# rotor.net
KiCad netlist of a schematic drawn in EAGLE
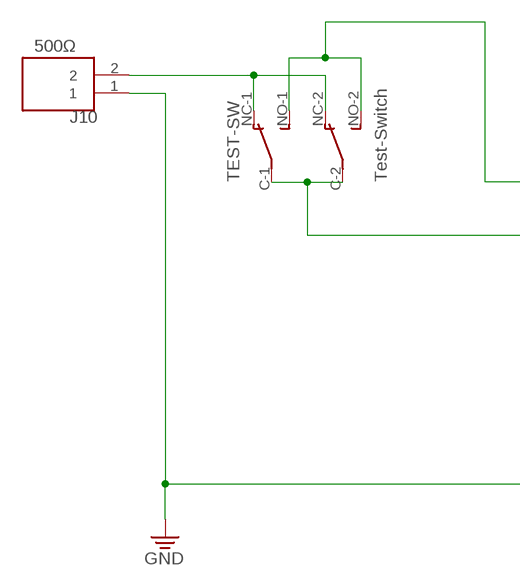
[diagram p0: schematic, sheet 1, part 1 of 2]
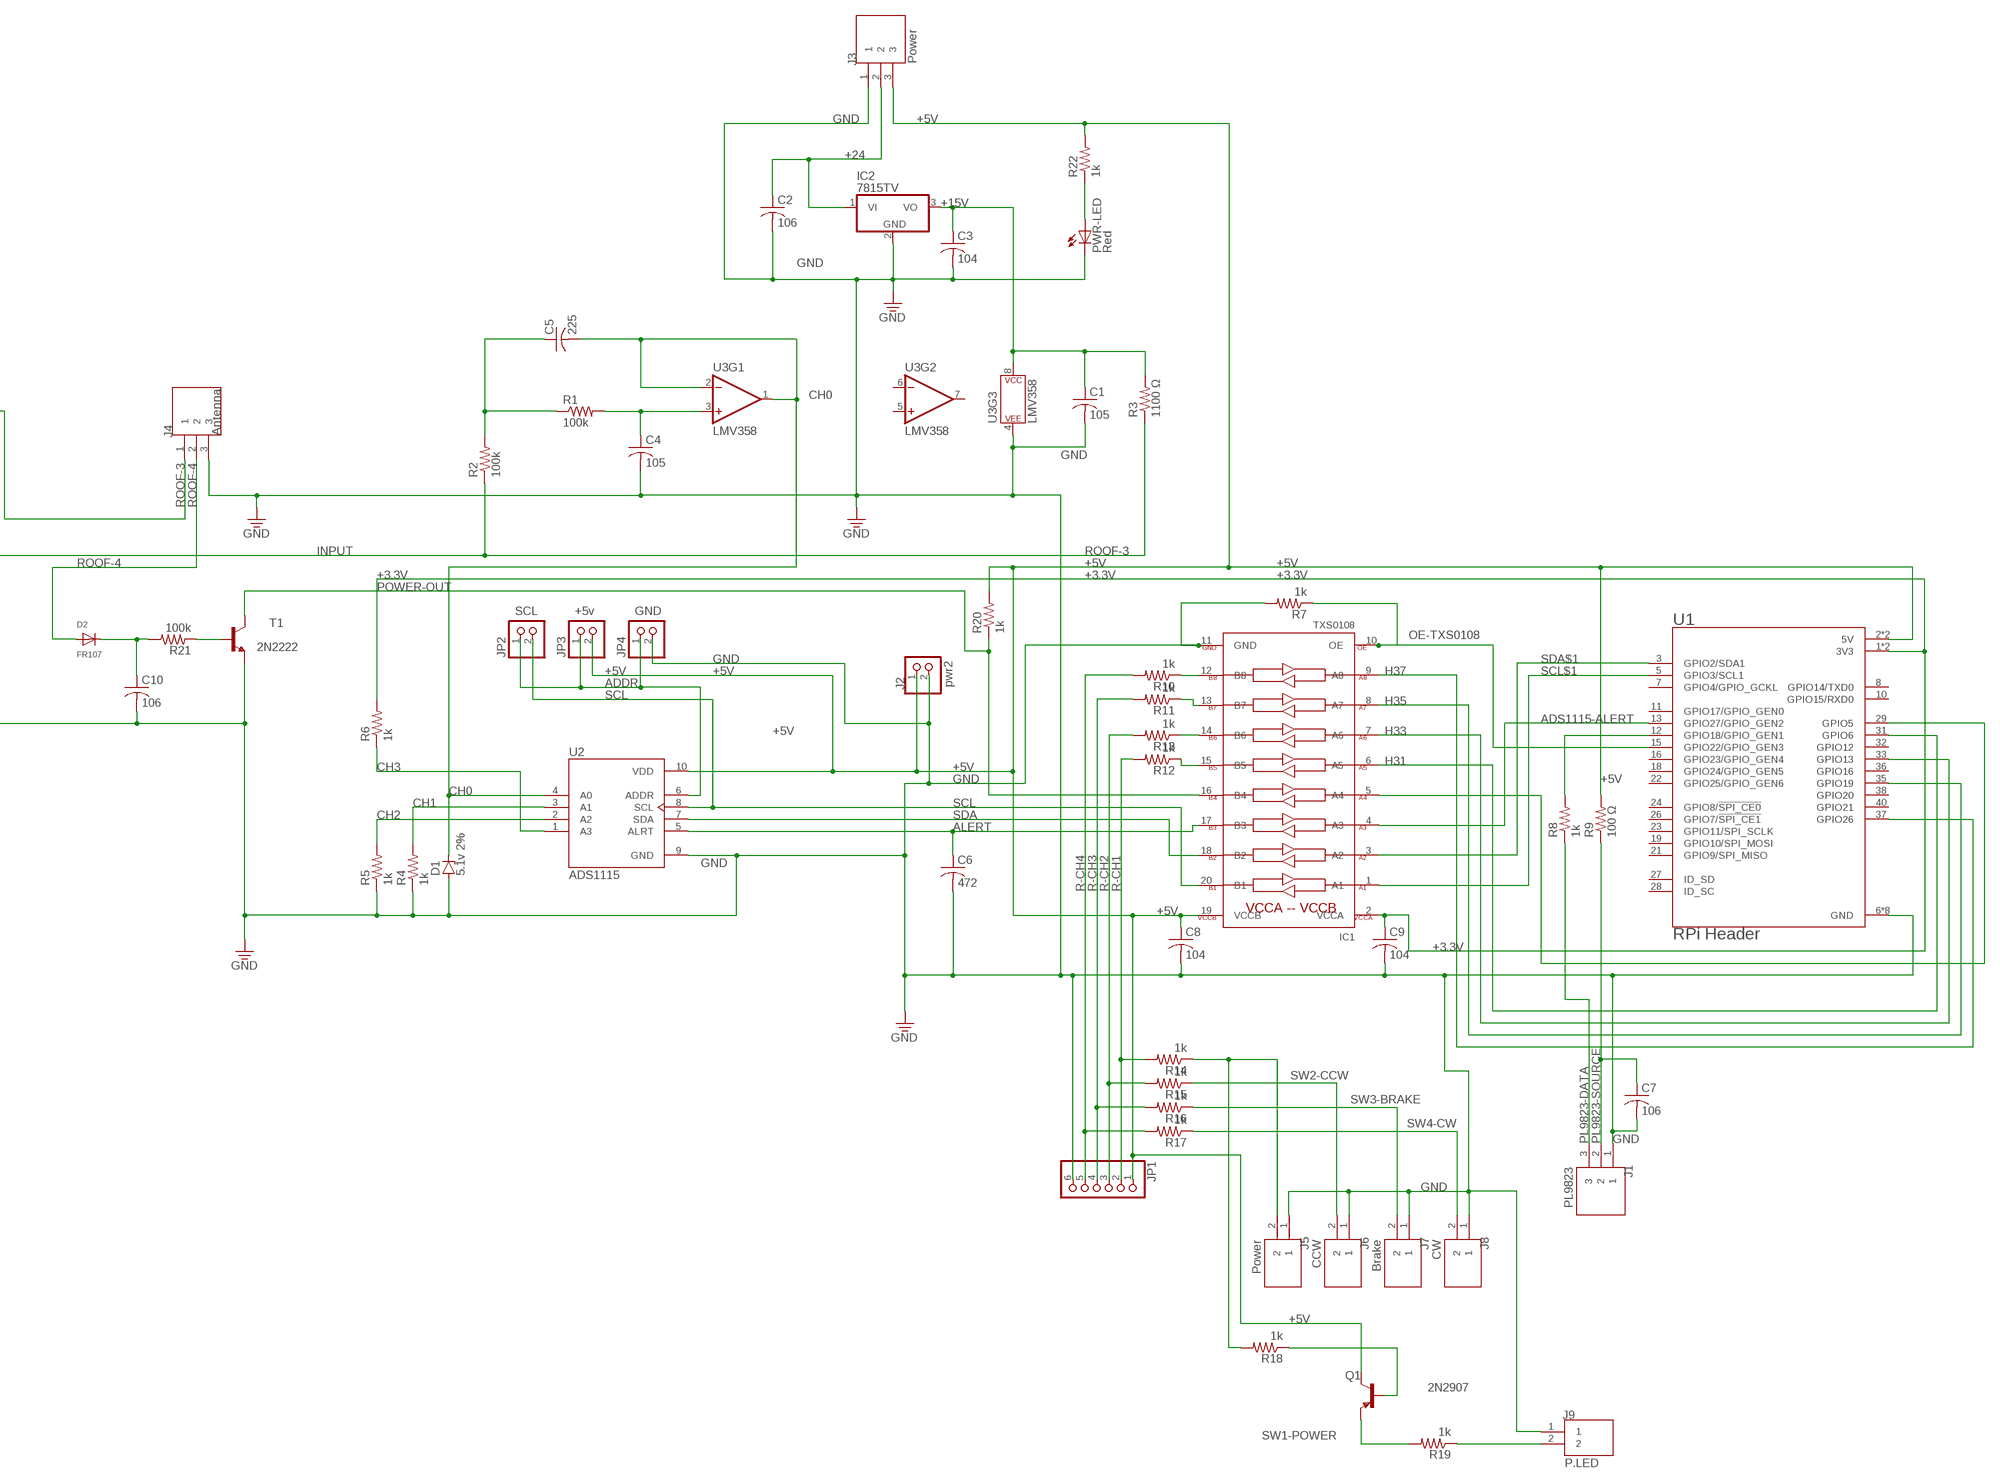
[diagram p1: schematic, sheet 1, part 2 of 2]

(export (version "E")
  (design (tool "Eeschema 10.0.6"))
  (components
    (comp (ref "C1")
      (value "105")
      (footprint "eagle-import:C0805")
      (libsource (lib "eagle-import") (part "C-USC0805"))
    )
    (comp (ref "C2")
      (value "106")
      (footprint "eagle-import:C0805")
      (libsource (lib "eagle-import") (part "C-USC0805"))
    )
    (comp (ref "C3")
      (value "104")
      (footprint "eagle-import:C0805")
      (libsource (lib "eagle-import") (part "C-USC0805"))
    )
    (comp (ref "C4")
      (value "105")
      (footprint "eagle-import:C0805")
      (libsource (lib "eagle-import") (part "C-USC0805"))
    )
    (comp (ref "C5")
      (value "225")
      (footprint "eagle-import:C0805")
      (libsource (lib "eagle-import") (part "C-USC0805"))
    )
    (comp (ref "C6")
      (value "472")
      (footprint "eagle-import:C0805")
      (libsource (lib "eagle-import") (part "C-USC0805"))
    )
    (comp (ref "C7")
      (value "106")
      (footprint "eagle-import:C0805")
      (libsource (lib "eagle-import") (part "C-USC0805"))
    )
    (comp (ref "C8")
      (value "104")
      (footprint "eagle-import:C0805")
      (libsource (lib "eagle-import") (part "C-USC0805"))
    )
    (comp (ref "C9")
      (value "104")
      (footprint "eagle-import:C0805")
      (libsource (lib "eagle-import") (part "C-USC0805"))
    )
    (comp (ref "C10")
      (value "106")
      (footprint "eagle-import:C0805")
      (libsource (lib "eagle-import") (part "C-USC0805"))
    )
    (comp (ref "D1")
      (value "5.1v 2%")
      (footprint "eagle-import:ZDIO-7.5")
      (libsource (lib "eagle-import") (part "ZENER-DIODEZD-7.5"))
    )
    (comp (ref "D2")
      (value "FR107")
      (footprint "eagle-import:SMADIODE")
      (libsource (lib "eagle-import") (part "DIODESMA"))
    )
    (comp (ref "IC1")
      (value "TXS0108")
      (footprint "eagle-import:TSSOP20")
      (fields (field (name "MF") "Texas Instruments") (field (name "MP") "TXS0108E"))
      (libsource (lib "eagle-import") (part "TXS0108EPWR"))
    )
    (comp (ref "IC2")
      (value "7815TV")
      (footprint "eagle-import:TO220V")
      (libsource (lib "eagle-import") (part "78TV15"))
    )
    (comp (ref "J1")
      (value "PL9823")
      (footprint "eagle-import:CUI_TB004-508-03BE")
      (fields (field (name "MF") "CUI Devices") (field (name "MP") "TB004 -508-03BE"))
      (libsource (lib "eagle-import") (part "TB004-508-03BE"))
    )
    (comp (ref "J2")
      (value "pwr2")
      (footprint "eagle-import:1X02")
      (libsource (lib "eagle-import") (part "pinhead_325_PINHD-1X2"))
    )
    (comp (ref "J3")
      (value "Power")
      (footprint "eagle-import:CUI_TB004-508-03BE")
      (fields (field (name "MF") "CUI Devices") (field (name "MP") "TB004 -508-03BE"))
      (libsource (lib "eagle-import") (part "TB004-508-03BE"))
    )
    (comp (ref "J4")
      (value "Antenna")
      (footprint "eagle-import:CUI_TB004-508-03BE")
      (fields (field (name "MF") "CUI Devices") (field (name "MP") "TB004 -508-03BE"))
      (libsource (lib "eagle-import") (part "TB004-508-03BE"))
    )
    (comp (ref "J5")
      (value "Power")
      (footprint "eagle-import:CUI_TB004-508-02BE")
      (fields (field (name "MF") "CUI Devices") (field (name "MP") "TB004-508-02BE"))
      (libsource (lib "eagle-import") (part "TB004-508-02BE"))
    )
    (comp (ref "J6")
      (value "CCW")
      (footprint "eagle-import:CUI_TB004-508-02BE")
      (fields (field (name "MF") "CUI Devices") (field (name "MP") "TB004-508-02BE"))
      (libsource (lib "eagle-import") (part "TB004-508-02BE"))
    )
    (comp (ref "J7")
      (value "Brake")
      (footprint "eagle-import:CUI_TB004-508-02BE")
      (fields (field (name "MF") "CUI Devices") (field (name "MP") "TB004-508-02BE"))
      (libsource (lib "eagle-import") (part "TB004-508-02BE"))
    )
    (comp (ref "J8")
      (value "CW")
      (footprint "eagle-import:CUI_TB004-508-02BE")
      (fields (field (name "MF") "CUI Devices") (field (name "MP") "TB004-508-02BE"))
      (libsource (lib "eagle-import") (part "TB004-508-02BE"))
    )
    (comp (ref "J9")
      (value "P.LED")
      (footprint "eagle-import:CUI_TB004-508-02BE")
      (fields (field (name "MF") "CUI Devices") (field (name "MP") "TB004-508-02BE"))
      (libsource (lib "eagle-import") (part "TB004-508-02BE"))
    )
    (comp (ref "J10")
      (value "500Ω ├")
      (footprint "eagle-import:CUI_TB004-508-02BE")
      (fields (field (name "MF") "CUI Devices") (field (name "MP") "TB004-508-02BE"))
      (libsource (lib "eagle-import") (part "TB004-508-02BE"))
    )
    (comp (ref "JP1")
      (value "PINHD-1X6")
      (footprint "eagle-import:1X06")
      (libsource (lib "eagle-import") (part "PINHD-1X6"))
    )
    (comp (ref "JP2")
      (value "SCL")
      (footprint "eagle-import:1X02-SPECIAL")
      (libsource (lib "eagle-import") (part "PINHD-1X2SPECIAL"))
    )
    (comp (ref "JP3")
      (value "+5v")
      (footprint "eagle-import:1X02-SPECIAL")
      (libsource (lib "eagle-import") (part "PINHD-1X2SPECIAL"))
    )
    (comp (ref "JP4")
      (value "GND")
      (footprint "eagle-import:1X02-SPECIAL")
      (libsource (lib "eagle-import") (part "PINHD-1X2SPECIAL"))
    )
    (comp (ref "PWR-LED")
      (value "Red")
      (footprint "eagle-import:CHIP-LED0805")
      (libsource (lib "eagle-import") (part "LEDCHIP-LED0805"))
    )
    (comp (ref "Q1")
      (value "2N2907")
      (footprint "eagle-import:TO92-EBC-OVAL")
      (libsource (lib "eagle-import") (part "2N2907EBC"))
    )
    (comp (ref "R1")
      (value "100k")
      (footprint "eagle-import:M0805")
      (libsource (lib "eagle-import") (part "test_R-US_M0805"))
    )
    (comp (ref "R2")
      (value "100k")
      (footprint "eagle-import:M0805")
      (libsource (lib "eagle-import") (part "test_R-US_M0805"))
    )
    (comp (ref "R3")
      (value "1100 Ω")
      (footprint "eagle-import:M0805")
      (libsource (lib "eagle-import") (part "R-US_M0805"))
    )
    (comp (ref "R4")
      (value "1k")
      (footprint "eagle-import:M0805")
      (libsource (lib "eagle-import") (part "test_R-US_M0805"))
    )
    (comp (ref "R5")
      (value "1k")
      (footprint "eagle-import:M0805")
      (libsource (lib "eagle-import") (part "test_R-US_M0805"))
    )
    (comp (ref "R6")
      (value "1k")
      (footprint "eagle-import:M0805")
      (libsource (lib "eagle-import") (part "test_R-US_M0805"))
    )
    (comp (ref "R7")
      (value "1k")
      (footprint "eagle-import:M0805")
      (libsource (lib "eagle-import") (part "test_R-US_M0805"))
    )
    (comp (ref "R8")
      (value "1k")
      (footprint "eagle-import:M0805")
      (libsource (lib "eagle-import") (part "test_R-US_M0805"))
    )
    (comp (ref "R9")
      (value "100 Ω")
      (footprint "eagle-import:M0805")
      (libsource (lib "eagle-import") (part "test_R-US_M0805"))
    )
    (comp (ref "R10")
      (value "1k")
      (footprint "eagle-import:M0805")
      (libsource (lib "eagle-import") (part "test_R-US_M0805"))
    )
    (comp (ref "R11")
      (value "1k")
      (footprint "eagle-import:M0805")
      (libsource (lib "eagle-import") (part "test_R-US_M0805"))
    )
    (comp (ref "R12")
      (value "1k")
      (footprint "eagle-import:M0805")
      (libsource (lib "eagle-import") (part "test_R-US_M0805"))
    )
    (comp (ref "R13")
      (value "1k")
      (footprint "eagle-import:M0805")
      (libsource (lib "eagle-import") (part "test_R-US_M0805"))
    )
    (comp (ref "R14")
      (value "1k")
      (footprint "eagle-import:M0805")
      (libsource (lib "eagle-import") (part "test_R-US_M0805"))
    )
    (comp (ref "R15")
      (value "1k")
      (footprint "eagle-import:M0805")
      (libsource (lib "eagle-import") (part "test_R-US_M0805"))
    )
    (comp (ref "R16")
      (value "1k")
      (footprint "eagle-import:M0805")
      (libsource (lib "eagle-import") (part "test_R-US_M0805"))
    )
    (comp (ref "R17")
      (value "1k")
      (footprint "eagle-import:M0805")
      (libsource (lib "eagle-import") (part "test_R-US_M0805"))
    )
    (comp (ref "R18")
      (value "1k")
      (footprint "eagle-import:M0805")
      (libsource (lib "eagle-import") (part "test_R-US_M0805"))
    )
    (comp (ref "R19")
      (value "1k")
      (footprint "eagle-import:M0805")
      (libsource (lib "eagle-import") (part "test_R-US_M0805"))
    )
    (comp (ref "R20")
      (value "1k")
      (footprint "eagle-import:M0805")
      (libsource (lib "eagle-import") (part "test_R-US_M0805"))
    )
    (comp (ref "R21")
      (value "100k")
      (footprint "eagle-import:M0805")
      (libsource (lib "eagle-import") (part "test_R-US_M0805"))
    )
    (comp (ref "R22")
      (value "1k")
      (footprint "eagle-import:M0805")
      (libsource (lib "eagle-import") (part "test_R-US_M0805"))
    )
    (comp (ref "T1")
      (value "2N2222")
      (footprint "eagle-import:TO92-EBC-OVAL")
      (libsource (lib "eagle-import") (part "2N2222EBC"))
    )
    (comp (ref "TEST-SW")
      (value "Test-Switch")
      (footprint "eagle-import:DP-DT")
      (libsource (lib "eagle-import") (part "DPDT-SWITCH"))
    )
    (comp (ref "U1")
      (value "RPi Header")
      (footprint "eagle-import:MODULE_RASPBERRY_PI_3B+_HDR")
      (libsource (lib "eagle-import") (part "RASPBERRY_PI_3B+_HDRMODEL_RASPBEERY_PI_3B_HDR"))
    )
    (comp (ref "U2")
      (value "ADS1115")
      (footprint "eagle-import:MODULE_1115_NARROW")
      (fields (field (name "MF") "Adafruit Industries") (field (name "MP") "1085"))
      (libsource (lib "eagle-import") (part "ADS1115-BREAKOUT-NARROW"))
    )
    (comp (ref "U3")
      (value "LMV358")
      (footprint "eagle-import:SO08")
      (libsource (lib "eagle-import") (part "LM358-SOP8SOIC"))
    )
  )
  (nets
    (net (code "1") (name "/+3.3V") (class "Default")
      (node (ref "C9") (pin "1") (pinfunction "1_1") (pintype "passive"))
      (node (ref "IC1") (pin "2") (pinfunction "VCCA_2") (pintype "power_in"))
      (node (ref "R6") (pin "2") (pinfunction "2_2") (pintype "passive"))
      (node (ref "U1") (pin "1") (pinfunction "3V3_1") (pintype "power_in"))
      (node (ref "U1") (pin "17") (pinfunction "3V3_17") (pintype "power_in"))
    )
    (net (code "2") (name "/+5V") (class "Default")
      (node (ref "C8") (pin "1") (pinfunction "1_1") (pintype "passive"))
      (node (ref "IC1") (pin "19") (pinfunction "VCCB_19") (pintype "power_in"))
      (node (ref "J2") (pin "1") (pinfunction "1_1") (pintype "passive"))
      (node (ref "J3") (pin "3") (pinfunction "3_3") (pintype "passive"))
      (node (ref "JP1") (pin "1") (pinfunction "1_1") (pintype "passive"))
      (node (ref "JP3") (pin "2") (pinfunction "2_2") (pintype "passive"))
      (node (ref "Q1") (pin "C") (pinfunction "C_C") (pintype "passive"))
      (node (ref "R20") (pin "2") (pinfunction "2_2") (pintype "passive"))
      (node (ref "R22") (pin "2") (pinfunction "2_2") (pintype "passive"))
      (node (ref "R9") (pin "2") (pinfunction "2_2") (pintype "passive"))
      (node (ref "U1") (pin "2") (pinfunction "5V_2") (pintype "power_in"))
      (node (ref "U1") (pin "4") (pinfunction "5V_4") (pintype "power_in"))
      (node (ref "U2") (pin "10") (pinfunction "VDD_10") (pintype "power_in"))
    )
    (net (code "3") (name "/+15V") (class "Default")
      (node (ref "C1") (pin "1") (pinfunction "1_1") (pintype "passive"))
      (node (ref "C3") (pin "1") (pinfunction "1_1") (pintype "passive"))
      (node (ref "IC2") (pin "3") (pinfunction "VO_3") (pintype "passive"))
      (node (ref "R3") (pin "2") (pinfunction "2_2") (pintype "passive"))
      (node (ref "U3") (pin "8") (pinfunction "P$V+_8") (pintype "bidirectional"))
    )
    (net (code "4") (name "/+24") (class "Default")
      (node (ref "C2") (pin "1") (pinfunction "1_1") (pintype "passive"))
      (node (ref "IC2") (pin "1") (pinfunction "VI_1") (pintype "input"))
      (node (ref "J3") (pin "2") (pinfunction "2_2") (pintype "passive"))
    )
    (net (code "5") (name "/ADDR") (class "Default")
      (node (ref "JP2") (pin "1") (pinfunction "1_1") (pintype "passive"))
      (node (ref "JP3") (pin "1") (pinfunction "1_1") (pintype "passive"))
      (node (ref "JP4") (pin "1") (pinfunction "1_1") (pintype "passive"))
      (node (ref "U2") (pin "6") (pinfunction "ADDR_6") (pintype "input"))
    )
    (net (code "6") (name "/ADS1115-ALERT") (class "Default")
      (node (ref "IC1") (pin "4") (pinfunction "A3_4") (pintype "bidirectional"))
      (node (ref "U1") (pin "13") (pinfunction "GPIO27/GPIO_GEN2_13") (pintype "bidirectional"))
    )
    (net (code "7") (name "/ALERT") (class "Default")
      (node (ref "C6") (pin "1") (pinfunction "1_1") (pintype "passive"))
      (node (ref "IC1") (pin "17") (pinfunction "B3_17") (pintype "bidirectional"))
      (node (ref "U2") (pin "5") (pinfunction "ALRT_5") (pintype "output"))
    )
    (net (code "8") (name "/CH0") (class "Default")
      (node (ref "C5") (pin "2") (pinfunction "2_2") (pintype "passive"))
      (node (ref "D1") (pin "C") (pinfunction "C_C") (pintype "passive"))
      (node (ref "U2") (pin "4") (pinfunction "A0_4") (pintype "input"))
      (node (ref "U3") (pin "1") (pinfunction "OUT_1") (pintype "output"))
      (node (ref "U3") (pin "2") (pinfunction "-IN_2") (pintype "input"))
    )
    (net (code "9") (name "/CH1") (class "Default")
      (node (ref "R4") (pin "2") (pinfunction "2_2") (pintype "passive"))
      (node (ref "U2") (pin "3") (pinfunction "A1_3") (pintype "input"))
    )
    (net (code "10") (name "/CH2") (class "Default")
      (node (ref "R5") (pin "2") (pinfunction "2_2") (pintype "passive"))
      (node (ref "U2") (pin "2") (pinfunction "A2_2") (pintype "input"))
    )
    (net (code "11") (name "/CH3") (class "Default")
      (node (ref "R6") (pin "1") (pinfunction "1_1") (pintype "passive"))
      (node (ref "U2") (pin "1") (pinfunction "A3_1") (pintype "input"))
    )
    (net (code "12") (name "/H31") (class "Default")
      (node (ref "IC1") (pin "6") (pinfunction "A5_6") (pintype "bidirectional"))
      (node (ref "U1") (pin "31") (pinfunction "GPIO6_31") (pintype "bidirectional"))
    )
    (net (code "13") (name "/H33") (class "Default")
      (node (ref "IC1") (pin "7") (pinfunction "A6_7") (pintype "bidirectional"))
      (node (ref "U1") (pin "33") (pinfunction "GPIO13_33") (pintype "bidirectional"))
    )
    (net (code "14") (name "/H35") (class "Default")
      (node (ref "IC1") (pin "8") (pinfunction "A7_8") (pintype "bidirectional"))
      (node (ref "U1") (pin "35") (pinfunction "GPIO19_35") (pintype "bidirectional"))
    )
    (net (code "15") (name "/H37") (class "Default")
      (node (ref "IC1") (pin "9") (pinfunction "A8_9") (pintype "bidirectional"))
      (node (ref "U1") (pin "37") (pinfunction "GPIO26_37") (pintype "bidirectional"))
    )
    (net (code "16") (name "/INPUT") (class "Default")
      (node (ref "R2") (pin "1") (pinfunction "1_1") (pintype "passive"))
      (node (ref "R3") (pin "1") (pinfunction "1_1") (pintype "passive"))
      (node (ref "TEST-SW") (pin "C-1") (pinfunction "C-1_C-1") (pintype "passive"))
      (node (ref "TEST-SW") (pin "C-2") (pinfunction "C-2_C-2") (pintype "passive"))
    )
    (net (code "17") (name "/OE-TXS0108") (class "Default")
      (node (ref "IC1") (pin "10") (pinfunction "OE_10") (pintype "input"))
      (node (ref "R7") (pin "1") (pinfunction "1_1") (pintype "passive"))
      (node (ref "U1") (pin "15") (pinfunction "GPIO22/GPIO_GEN3_15") (pintype "bidirectional"))
    )
    (net (code "18") (name "/PL9823-DATA") (class "Default")
      (node (ref "J1") (pin "3") (pinfunction "3_3") (pintype "passive"))
      (node (ref "R8") (pin "1") (pinfunction "1_1") (pintype "passive"))
    )
    (net (code "19") (name "/PL9823-SOURCE") (class "Default")
      (node (ref "C7") (pin "1") (pinfunction "1_1") (pintype "passive"))
      (node (ref "J1") (pin "2") (pinfunction "2_2") (pintype "passive"))
      (node (ref "R9") (pin "1") (pinfunction "1_1") (pintype "passive"))
    )
    (net (code "20") (name "/POWER-OUT") (class "Default")
      (node (ref "IC1") (pin "16") (pinfunction "B4_16") (pintype "bidirectional"))
      (node (ref "R20") (pin "1") (pinfunction "1_1") (pintype "passive"))
      (node (ref "T1") (pin "C") (pinfunction "C_C") (pintype "passive"))
    )
    (net (code "21") (name "/R-CH1") (class "Default")
      (node (ref "JP1") (pin "2") (pinfunction "2_2") (pintype "passive"))
      (node (ref "R12") (pin "2") (pinfunction "2_2") (pintype "passive"))
      (node (ref "R14") (pin "2") (pinfunction "2_2") (pintype "passive"))
    )
    (net (code "22") (name "/R-CH2") (class "Default")
      (node (ref "JP1") (pin "3") (pinfunction "3_3") (pintype "passive"))
      (node (ref "R13") (pin "2") (pinfunction "2_2") (pintype "passive"))
      (node (ref "R15") (pin "2") (pinfunction "2_2") (pintype "passive"))
    )
    (net (code "23") (name "/R-CH3") (class "Default")
      (node (ref "JP1") (pin "4") (pinfunction "4_4") (pintype "passive"))
      (node (ref "R11") (pin "2") (pinfunction "2_2") (pintype "passive"))
      (node (ref "R16") (pin "2") (pinfunction "2_2") (pintype "passive"))
    )
    (net (code "24") (name "/R-CH4") (class "Default")
      (node (ref "JP1") (pin "5") (pinfunction "5_5") (pintype "passive"))
      (node (ref "R10") (pin "2") (pinfunction "2_2") (pintype "passive"))
      (node (ref "R17") (pin "2") (pinfunction "2_2") (pintype "passive"))
    )
    (net (code "25") (name "/ROOF-3") (class "Default")
      (node (ref "J4") (pin "1") (pinfunction "1_1") (pintype "passive"))
      (node (ref "TEST-SW") (pin "NO-1") (pinfunction "NO-1_NO-1") (pintype "passive"))
      (node (ref "TEST-SW") (pin "NO-2") (pinfunction "NO-2_NO-2") (pintype "passive"))
    )
    (net (code "26") (name "/ROOF-4") (class "Default")
      (node (ref "D2") (pin "A") (pinfunction "A_A") (pintype "passive"))
      (node (ref "J4") (pin "2") (pinfunction "2_2") (pintype "passive"))
    )
    (net (code "27") (name "/SCL") (class "Default")
      (node (ref "IC1") (pin "20") (pinfunction "B1_20") (pintype "bidirectional"))
      (node (ref "JP2") (pin "2") (pinfunction "2_2") (pintype "passive"))
      (node (ref "U2") (pin "8") (pinfunction "SCL_8") (pintype "input"))
    )
    (net (code "28") (name "/SCL$1") (class "Default")
      (node (ref "IC1") (pin "1") (pinfunction "A1_1") (pintype "bidirectional"))
      (node (ref "U1") (pin "5") (pinfunction "GPIO3/SCL1_5") (pintype "bidirectional"))
    )
    (net (code "29") (name "/SDA") (class "Default")
      (node (ref "IC1") (pin "18") (pinfunction "B2_18") (pintype "bidirectional"))
      (node (ref "U2") (pin "7") (pinfunction "SDA_7") (pintype "bidirectional"))
    )
    (net (code "30") (name "/SDA$1") (class "Default")
      (node (ref "IC1") (pin "3") (pinfunction "A2_3") (pintype "bidirectional"))
      (node (ref "U1") (pin "3") (pinfunction "GPIO2/SDA1_3") (pintype "bidirectional"))
    )
    (net (code "31") (name "/SW1-POWER") (class "Default")
      (node (ref "J5") (pin "2") (pinfunction "2_2") (pintype "passive"))
      (node (ref "R14") (pin "1") (pinfunction "1_1") (pintype "passive"))
      (node (ref "R18") (pin "2") (pinfunction "2_2") (pintype "passive"))
    )
    (net (code "32") (name "/SW2-CCW") (class "Default")
      (node (ref "J6") (pin "2") (pinfunction "2_2") (pintype "passive"))
      (node (ref "R15") (pin "1") (pinfunction "1_1") (pintype "passive"))
    )
    (net (code "33") (name "/SW3-BRAKE") (class "Default")
      (node (ref "J7") (pin "2") (pinfunction "2_2") (pintype "passive"))
      (node (ref "R16") (pin "1") (pinfunction "1_1") (pintype "passive"))
    )
    (net (code "34") (name "/SW4-CW") (class "Default")
      (node (ref "J8") (pin "2") (pinfunction "2_2") (pintype "passive"))
      (node (ref "R17") (pin "1") (pinfunction "1_1") (pintype "passive"))
    )
    (net (code "35") (name "GND") (class "Default")
      (node (ref "C1") (pin "2") (pinfunction "2_2") (pintype "passive"))
      (node (ref "C10") (pin "2") (pinfunction "2_2") (pintype "passive"))
      (node (ref "C2") (pin "2") (pinfunction "2_2") (pintype "passive"))
      (node (ref "C3") (pin "2") (pinfunction "2_2") (pintype "passive"))
      (node (ref "C4") (pin "2") (pinfunction "2_2") (pintype "passive"))
      (node (ref "C6") (pin "2") (pinfunction "2_2") (pintype "passive"))
      (node (ref "C7") (pin "2") (pinfunction "2_2") (pintype "passive"))
      (node (ref "C8") (pin "2") (pinfunction "2_2") (pintype "passive"))
      (node (ref "C9") (pin "2") (pinfunction "2_2") (pintype "passive"))
      (node (ref "D1") (pin "A") (pinfunction "A_A") (pintype "passive"))
      (node (ref "IC1") (pin "11") (pinfunction "GND_11") (pintype "power_in"))
      (node (ref "IC2") (pin "2") (pinfunction "GND_2") (pintype "passive"))
      (node (ref "J1") (pin "1") (pinfunction "1_1") (pintype "passive"))
      (node (ref "J10") (pin "1") (pinfunction "1_1") (pintype "passive"))
      (node (ref "J2") (pin "2") (pinfunction "2_2") (pintype "passive"))
      (node (ref "J3") (pin "1") (pinfunction "1_1") (pintype "passive"))
      (node (ref "J4") (pin "3") (pinfunction "3_3") (pintype "passive"))
      (node (ref "J5") (pin "1") (pinfunction "1_1") (pintype "passive"))
      (node (ref "J6") (pin "1") (pinfunction "1_1") (pintype "passive"))
      (node (ref "J7") (pin "1") (pinfunction "1_1") (pintype "passive"))
      (node (ref "J8") (pin "1") (pinfunction "1_1") (pintype "passive"))
      (node (ref "J9") (pin "1") (pinfunction "1_1") (pintype "passive"))
      (node (ref "JP1") (pin "6") (pinfunction "6_6") (pintype "passive"))
      (node (ref "JP4") (pin "2") (pinfunction "2_2") (pintype "passive"))
      (node (ref "PWR-LED") (pin "C") (pinfunction "C_C") (pintype "passive"))
      (node (ref "R4") (pin "1") (pinfunction "1_1") (pintype "passive"))
      (node (ref "R5") (pin "1") (pinfunction "1_1") (pintype "passive"))
      (node (ref "R7") (pin "2") (pinfunction "2_2") (pintype "passive"))
      (node (ref "T1") (pin "E") (pinfunction "E_E") (pintype "passive"))
      (node (ref "U1") (pin "14") (pinfunction "GND_14") (pintype "power_in"))
      (node (ref "U1") (pin "20") (pinfunction "GND_20") (pintype "power_in"))
      (node (ref "U1") (pin "25") (pinfunction "GND_25") (pintype "power_in"))
      (node (ref "U1") (pin "30") (pinfunction "GND_30") (pintype "power_in"))
      (node (ref "U1") (pin "34") (pinfunction "GND_34") (pintype "power_in"))
      (node (ref "U1") (pin "39") (pinfunction "GND_39") (pintype "power_in"))
      (node (ref "U1") (pin "6") (pinfunction "GND_6") (pintype "power_in"))
      (node (ref "U1") (pin "9") (pinfunction "GND_9") (pintype "power_in"))
      (node (ref "U2") (pin "9") (pinfunction "GND_9") (pintype "power_in"))
      (node (ref "U3") (pin "4") (pinfunction "P$V-_4") (pintype "bidirectional"))
    )
    (net (code "36") (name "Net-(C5-Pad1)") (class "Default")
      (node (ref "C5") (pin "1") (pinfunction "1_1") (pintype "passive"))
      (node (ref "R1") (pin "1") (pinfunction "1_1") (pintype "passive"))
      (node (ref "R2") (pin "2") (pinfunction "2_2") (pintype "passive"))
    )
    (net (code "37") (name "Net-(C10-Pad1)") (class "Default")
      (node (ref "C10") (pin "1") (pinfunction "1_1") (pintype "passive"))
      (node (ref "D2") (pin "C") (pinfunction "C_C") (pintype "passive"))
      (node (ref "R21") (pin "2") (pinfunction "2_2") (pintype "passive"))
    )
    (net (code "38") (name "Net-(IC1-A4)") (class "Default")
      (node (ref "IC1") (pin "5") (pinfunction "A4_5") (pintype "bidirectional"))
      (node (ref "U1") (pin "29") (pinfunction "GPIO5_29") (pintype "bidirectional"))
    )
    (net (code "39") (name "Net-(IC1-B5)") (class "Default")
      (node (ref "IC1") (pin "15") (pinfunction "B5_15") (pintype "bidirectional"))
      (node (ref "R12") (pin "1") (pinfunction "1_1") (pintype "passive"))
    )
    (net (code "40") (name "Net-(IC1-B6)") (class "Default")
      (node (ref "IC1") (pin "14") (pinfunction "B6_14") (pintype "bidirectional"))
      (node (ref "R13") (pin "1") (pinfunction "1_1") (pintype "passive"))
    )
    (net (code "41") (name "Net-(IC1-B7)") (class "Default")
      (node (ref "IC1") (pin "13") (pinfunction "B7_13") (pintype "bidirectional"))
      (node (ref "R11") (pin "1") (pinfunction "1_1") (pintype "passive"))
    )
    (net (code "42") (name "Net-(IC1-B8)") (class "Default")
      (node (ref "IC1") (pin "12") (pinfunction "B8_12") (pintype "bidirectional"))
      (node (ref "R10") (pin "1") (pinfunction "1_1") (pintype "passive"))
    )
    (net (code "43") (name "Net-(J9-Pad2)") (class "Default")
      (node (ref "J9") (pin "2") (pinfunction "2_2") (pintype "passive"))
      (node (ref "R19") (pin "1") (pinfunction "1_1") (pintype "passive"))
    )
    (net (code "44") (name "Net-(J10-Pad2)") (class "Default")
      (node (ref "J10") (pin "2") (pinfunction "2_2") (pintype "passive"))
      (node (ref "TEST-SW") (pin "NC-1") (pinfunction "NC-1_NC-1") (pintype "passive"))
      (node (ref "TEST-SW") (pin "NC-2") (pinfunction "NC-2_NC-2") (pintype "passive"))
    )
    (net (code "45") (name "Net-(PWR-LED-PadA)") (class "Default")
      (node (ref "PWR-LED") (pin "A") (pinfunction "A_A") (pintype "passive"))
      (node (ref "R22") (pin "1") (pinfunction "1_1") (pintype "passive"))
    )
    (net (code "46") (name "Net-(Q1-PadB)") (class "Default")
      (node (ref "Q1") (pin "B") (pinfunction "B_B") (pintype "passive"))
      (node (ref "R18") (pin "1") (pinfunction "1_1") (pintype "passive"))
    )
    (net (code "47") (name "Net-(Q1-PadE)") (class "Default")
      (node (ref "Q1") (pin "E") (pinfunction "E_E") (pintype "passive"))
      (node (ref "R19") (pin "2") (pinfunction "2_2") (pintype "passive"))
    )
    (net (code "48") (name "Net-(R21-Pad1)") (class "Default")
      (node (ref "R21") (pin "1") (pinfunction "1_1") (pintype "passive"))
      (node (ref "T1") (pin "B") (pinfunction "B_B") (pintype "passive"))
    )
    (net (code "49") (name "Net-(U1-GPIO18{slash}GPIO_GEN1)") (class "Default")
      (node (ref "R8") (pin "2") (pinfunction "2_2") (pintype "passive"))
      (node (ref "U1") (pin "12") (pinfunction "GPIO18/GPIO_GEN1_12") (pintype "bidirectional"))
    )
    (net (code "50") (name "Net-(U3A-+IN)") (class "Default")
      (node (ref "C4") (pin "1") (pinfunction "1_1") (pintype "passive"))
      (node (ref "R1") (pin "2") (pinfunction "2_2") (pintype "passive"))
      (node (ref "U3") (pin "3") (pinfunction "+IN_3") (pintype "input"))
    )
    (net (code "51") (name "unconnected-(U1-GPIO4{slash}GPIO_GCKL-Pad7)") (class "Default")
      (node (ref "U1") (pin "7") (pinfunction "GPIO4/GPIO_GCKL_7") (pintype "bidirectional"))
    )
    (net (code "52") (name "unconnected-(U1-GPIO7{slash}~{SPI_CE1}-Pad26)") (class "Default")
      (node (ref "U1") (pin "26") (pinfunction "GPIO7/~{SPI_CE1}_26") (pintype "bidirectional"))
    )
    (net (code "53") (name "unconnected-(U1-GPIO8{slash}~{SPI_CE0}-Pad24)") (class "Default")
      (node (ref "U1") (pin "24") (pinfunction "GPIO8/~{SPI_CE0}_24") (pintype "bidirectional"))
    )
    (net (code "54") (name "unconnected-(U1-GPIO9{slash}SPI_MISO-Pad21)") (class "Default")
      (node (ref "U1") (pin "21") (pinfunction "GPIO9/SPI_MISO_21") (pintype "bidirectional"))
    )
    (net (code "55") (name "unconnected-(U1-GPIO10{slash}SPI_MOSI-Pad19)") (class "Default")
      (node (ref "U1") (pin "19") (pinfunction "GPIO10/SPI_MOSI_19") (pintype "bidirectional"))
    )
    (net (code "56") (name "unconnected-(U1-GPIO11{slash}SPI_SCLK-Pad23)") (class "Default")
      (node (ref "U1") (pin "23") (pinfunction "GPIO11/SPI_SCLK_23") (pintype "bidirectional"))
    )
    (net (code "57") (name "unconnected-(U1-GPIO12-Pad32)") (class "Default")
      (node (ref "U1") (pin "32") (pinfunction "GPIO12_32") (pintype "bidirectional"))
    )
    (net (code "58") (name "unconnected-(U1-GPIO14{slash}TXD0-Pad8)") (class "Default")
      (node (ref "U1") (pin "8") (pinfunction "GPIO14/TXD0_8") (pintype "bidirectional"))
    )
    (net (code "59") (name "unconnected-(U1-GPIO15{slash}RXD0-Pad10)") (class "Default")
      (node (ref "U1") (pin "10") (pinfunction "GPIO15/RXD0_10") (pintype "bidirectional"))
    )
    (net (code "60") (name "unconnected-(U1-GPIO16-Pad36)") (class "Default")
      (node (ref "U1") (pin "36") (pinfunction "GPIO16_36") (pintype "bidirectional"))
    )
    (net (code "61") (name "unconnected-(U1-GPIO17{slash}GPIO_GEN0-Pad11)") (class "Default")
      (node (ref "U1") (pin "11") (pinfunction "GPIO17/GPIO_GEN0_11") (pintype "bidirectional"))
    )
    (net (code "62") (name "unconnected-(U1-GPIO20-Pad38)") (class "Default")
      (node (ref "U1") (pin "38") (pinfunction "GPIO20_38") (pintype "bidirectional"))
    )
    (net (code "63") (name "unconnected-(U1-GPIO21-Pad40)") (class "Default")
      (node (ref "U1") (pin "40") (pinfunction "GPIO21_40") (pintype "bidirectional"))
    )
    (net (code "64") (name "unconnected-(U1-GPIO23{slash}GPIO_GEN4-Pad16)") (class "Default")
      (node (ref "U1") (pin "16") (pinfunction "GPIO23/GPIO_GEN4_16") (pintype "bidirectional"))
    )
    (net (code "65") (name "unconnected-(U1-GPIO24{slash}GPIO_GEN5-Pad18)") (class "Default")
      (node (ref "U1") (pin "18") (pinfunction "GPIO24/GPIO_GEN5_18") (pintype "bidirectional"))
    )
    (net (code "66") (name "unconnected-(U1-GPIO25{slash}GPIO_GEN6-Pad22)") (class "Default")
      (node (ref "U1") (pin "22") (pinfunction "GPIO25/GPIO_GEN6_22") (pintype "bidirectional"))
    )
    (net (code "67") (name "unconnected-(U1-ID_SC-Pad28)") (class "Default")
      (node (ref "U1") (pin "28") (pinfunction "ID_SC_28") (pintype "bidirectional"))
    )
    (net (code "68") (name "unconnected-(U1-ID_SD-Pad27)") (class "Default")
      (node (ref "U1") (pin "27") (pinfunction "ID_SD_27") (pintype "bidirectional"))
    )
    (net (code "69") (name "unconnected-(U3B-+IN-Pad5)") (class "Default")
      (node (ref "U3") (pin "5") (pinfunction "+IN_5") (pintype "input"))
    )
    (net (code "70") (name "unconnected-(U3B--IN-Pad6)") (class "Default")
      (node (ref "U3") (pin "6") (pinfunction "-IN_6") (pintype "input"))
    )
    (net (code "71") (name "unconnected-(U3B-OUT-Pad7)") (class "Default")
      (node (ref "U3") (pin "7") (pinfunction "OUT_7") (pintype "output"))
    )
  )
)
